# AtmoOrb.net
KiCad netlist of a schematic drawn in EAGLE
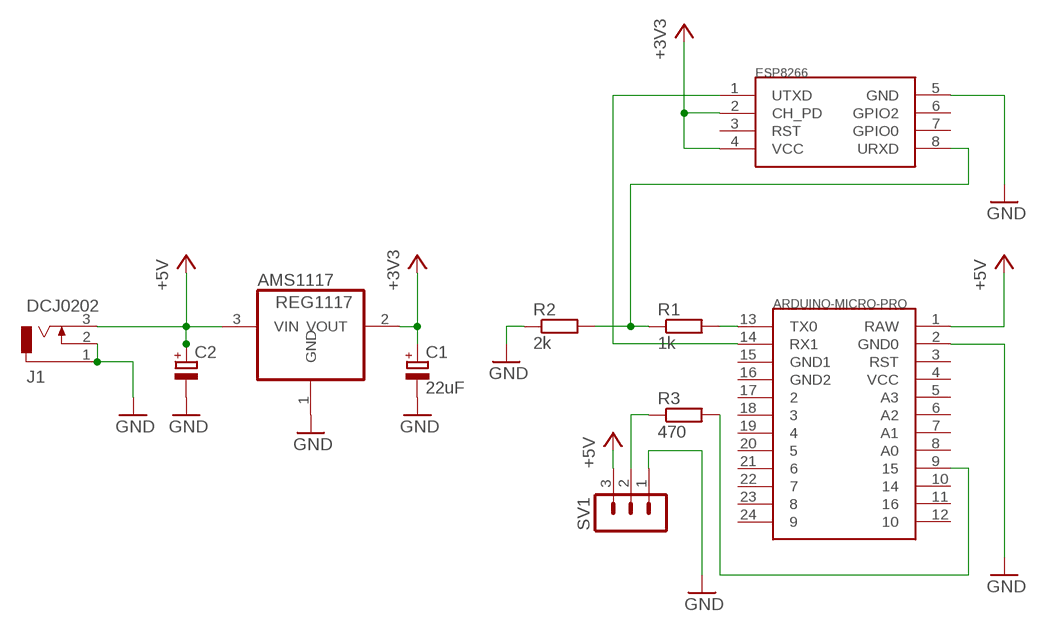
[diagram p0: schematic, sheet 1]

(export (version "E")
  (design (tool "Eeschema 10.0.6"))
  (components
    (comp (ref "AMS1117")
      (value "REG1117")
      (footprint "eagle-import:SOT223")
      (libsource (lib "eagle-import") (part "REG1117"))
    )
    (comp (ref "ARDUINO-MICRO-PRO")
      (value "ARDUINO_MICRO_PRO")
      (footprint "eagle-import:ARDUINO_MICRO_PRO")
      (libsource (lib "eagle-import") (part "ARDUINO_MICRO_PRO"))
    )
    (comp (ref "C1")
      (value "22uF")
      (footprint "eagle-import:TAP5-60")
      (libsource (lib "eagle-import") (part "CPOL-EUTAP5-60"))
    )
    (comp (ref "C2")
      (value "CPOL-EUTAP5-60")
      (footprint "eagle-import:TAP5-60")
      (libsource (lib "eagle-import") (part "CPOL-EUTAP5-60"))
    )
    (comp (ref "ESP8266")
      (value "ESP8266")
      (footprint "eagle-import:ESP8266")
      (libsource (lib "eagle-import") (part "ESP8266"))
    )
    (comp (ref "J1")
      (value "DCJ0202")
      (footprint "eagle-import:DCJ0202")
      (libsource (lib "eagle-import") (part "DCJ0202"))
    )
    (comp (ref "R1")
      (value "1k")
      (footprint "eagle-import:0207_10")
      (libsource (lib "eagle-import") (part "R-EU_0207/10"))
    )
    (comp (ref "R2")
      (value "2k")
      (footprint "eagle-import:0207_10")
      (libsource (lib "eagle-import") (part "R-EU_0207/10"))
    )
    (comp (ref "R3")
      (value "470")
      (footprint "eagle-import:0207_10")
      (libsource (lib "eagle-import") (part "R-EU_0207/10"))
    )
    (comp (ref "SV1")
      (value "MA03-1")
      (footprint "eagle-import:MA03-1")
      (libsource (lib "eagle-import") (part "MA03-1"))
    )
  )
  (nets
    (net (code "1") (name "+3V3") (class "Default")
      (node (ref "AMS1117") (pin "2") (pinfunction "VOUT_2") (pintype "output"))
      (node (ref "C1") (pin "+") (pinfunction "+_+") (pintype "passive"))
      (node (ref "ESP8266") (pin "2") (pinfunction "CH_PD_2") (pintype "bidirectional"))
      (node (ref "ESP8266") (pin "4") (pinfunction "VCC_4") (pintype "bidirectional"))
    )
    (net (code "2") (name "+5V") (class "Default")
      (node (ref "AMS1117") (pin "3") (pinfunction "VIN_3") (pintype "input"))
      (node (ref "ARDUINO-MICRO-PRO") (pin "1") (pinfunction "RAW_1") (pintype "bidirectional"))
      (node (ref "C2") (pin "+") (pinfunction "+_+") (pintype "passive"))
      (node (ref "J1") (pin "3") (pinfunction "3_3") (pintype "passive"))
      (node (ref "SV1") (pin "3") (pinfunction "3_3") (pintype "passive"))
    )
    (net (code "3") (name "GND") (class "Default")
      (node (ref "AMS1117") (pin "1") (pinfunction "GND_1") (pintype "power_in"))
      (node (ref "ARDUINO-MICRO-PRO") (pin "2") (pinfunction "GND0_2") (pintype "bidirectional"))
      (node (ref "C1") (pin "-") (pinfunction "-_-") (pintype "passive"))
      (node (ref "C2") (pin "-") (pinfunction "-_-") (pintype "passive"))
      (node (ref "ESP8266") (pin "5") (pinfunction "GND_5") (pintype "bidirectional"))
      (node (ref "J1") (pin "1") (pinfunction "1_1") (pintype "passive"))
      (node (ref "J1") (pin "2") (pinfunction "2_2") (pintype "passive"))
      (node (ref "R2") (pin "1") (pinfunction "1_1") (pintype "passive"))
      (node (ref "SV1") (pin "1") (pinfunction "1_1") (pintype "passive"))
    )
    (net (code "4") (name "Net-(ARDUINO-MICRO-PRO-15)") (class "Default")
      (node (ref "ARDUINO-MICRO-PRO") (pin "9") (pinfunction "15_9") (pintype "bidirectional"))
      (node (ref "R3") (pin "2") (pinfunction "2_2") (pintype "passive"))
    )
    (net (code "5") (name "Net-(ARDUINO-MICRO-PRO-RX1)") (class "Default")
      (node (ref "ARDUINO-MICRO-PRO") (pin "14") (pinfunction "RX1_14") (pintype "bidirectional"))
      (node (ref "ESP8266") (pin "1") (pinfunction "UTXD_1") (pintype "bidirectional"))
    )
    (net (code "6") (name "Net-(ARDUINO-MICRO-PRO-TX0)") (class "Default")
      (node (ref "ARDUINO-MICRO-PRO") (pin "13") (pinfunction "TX0_13") (pintype "bidirectional"))
      (node (ref "R1") (pin "2") (pinfunction "2_2") (pintype "passive"))
    )
    (net (code "7") (name "Net-(ESP8266-URXD)") (class "Default")
      (node (ref "ESP8266") (pin "8") (pinfunction "URXD_8") (pintype "bidirectional"))
      (node (ref "R1") (pin "1") (pinfunction "1_1") (pintype "passive"))
      (node (ref "R2") (pin "2") (pinfunction "2_2") (pintype "passive"))
    )
    (net (code "8") (name "Net-(R3-Pad1)") (class "Default")
      (node (ref "R3") (pin "1") (pinfunction "1_1") (pintype "passive"))
      (node (ref "SV1") (pin "2") (pinfunction "2_2") (pintype "passive"))
    )
    (net (code "9") (name "unconnected-(ARDUINO-MICRO-PRO-2-Pad17)") (class "Default")
      (node (ref "ARDUINO-MICRO-PRO") (pin "17") (pinfunction "2_17") (pintype "bidirectional"))
    )
    (net (code "10") (name "unconnected-(ARDUINO-MICRO-PRO-3-Pad18)") (class "Default")
      (node (ref "ARDUINO-MICRO-PRO") (pin "18") (pinfunction "3_18") (pintype "bidirectional"))
    )
    (net (code "11") (name "unconnected-(ARDUINO-MICRO-PRO-4-Pad19)") (class "Default")
      (node (ref "ARDUINO-MICRO-PRO") (pin "19") (pinfunction "4_19") (pintype "bidirectional"))
    )
    (net (code "12") (name "unconnected-(ARDUINO-MICRO-PRO-5-Pad20)") (class "Default")
      (node (ref "ARDUINO-MICRO-PRO") (pin "20") (pinfunction "5_20") (pintype "bidirectional"))
    )
    (net (code "13") (name "unconnected-(ARDUINO-MICRO-PRO-6-Pad21)") (class "Default")
      (node (ref "ARDUINO-MICRO-PRO") (pin "21") (pinfunction "6_21") (pintype "bidirectional"))
    )
    (net (code "14") (name "unconnected-(ARDUINO-MICRO-PRO-7-Pad22)") (class "Default")
      (node (ref "ARDUINO-MICRO-PRO") (pin "22") (pinfunction "7_22") (pintype "bidirectional"))
    )
    (net (code "15") (name "unconnected-(ARDUINO-MICRO-PRO-8-Pad23)") (class "Default")
      (node (ref "ARDUINO-MICRO-PRO") (pin "23") (pinfunction "8_23") (pintype "bidirectional"))
    )
    (net (code "16") (name "unconnected-(ARDUINO-MICRO-PRO-9-Pad24)") (class "Default")
      (node (ref "ARDUINO-MICRO-PRO") (pin "24") (pinfunction "9_24") (pintype "bidirectional"))
    )
    (net (code "17") (name "unconnected-(ARDUINO-MICRO-PRO-10-Pad12)") (class "Default")
      (node (ref "ARDUINO-MICRO-PRO") (pin "12") (pinfunction "10_12") (pintype "bidirectional"))
    )
    (net (code "18") (name "unconnected-(ARDUINO-MICRO-PRO-14-Pad10)") (class "Default")
      (node (ref "ARDUINO-MICRO-PRO") (pin "10") (pinfunction "14_10") (pintype "bidirectional"))
    )
    (net (code "19") (name "unconnected-(ARDUINO-MICRO-PRO-16-Pad11)") (class "Default")
      (node (ref "ARDUINO-MICRO-PRO") (pin "11") (pinfunction "16_11") (pintype "bidirectional"))
    )
    (net (code "20") (name "unconnected-(ARDUINO-MICRO-PRO-A0-Pad8)") (class "Default")
      (node (ref "ARDUINO-MICRO-PRO") (pin "8") (pinfunction "A0_8") (pintype "bidirectional"))
    )
    (net (code "21") (name "unconnected-(ARDUINO-MICRO-PRO-A1-Pad7)") (class "Default")
      (node (ref "ARDUINO-MICRO-PRO") (pin "7") (pinfunction "A1_7") (pintype "bidirectional"))
    )
    (net (code "22") (name "unconnected-(ARDUINO-MICRO-PRO-A2-Pad6)") (class "Default")
      (node (ref "ARDUINO-MICRO-PRO") (pin "6") (pinfunction "A2_6") (pintype "bidirectional"))
    )
    (net (code "23") (name "unconnected-(ARDUINO-MICRO-PRO-A3-Pad5)") (class "Default")
      (node (ref "ARDUINO-MICRO-PRO") (pin "5") (pinfunction "A3_5") (pintype "bidirectional"))
    )
    (net (code "24") (name "unconnected-(ARDUINO-MICRO-PRO-GND1-Pad15)") (class "Default")
      (node (ref "ARDUINO-MICRO-PRO") (pin "15") (pinfunction "GND1_15") (pintype "bidirectional"))
    )
    (net (code "25") (name "unconnected-(ARDUINO-MICRO-PRO-GND2-Pad16)") (class "Default")
      (node (ref "ARDUINO-MICRO-PRO") (pin "16") (pinfunction "GND2_16") (pintype "bidirectional"))
    )
    (net (code "26") (name "unconnected-(ARDUINO-MICRO-PRO-RST-Pad3)") (class "Default")
      (node (ref "ARDUINO-MICRO-PRO") (pin "3") (pinfunction "RST_3") (pintype "bidirectional"))
    )
    (net (code "27") (name "unconnected-(ARDUINO-MICRO-PRO-VCC-Pad4)") (class "Default")
      (node (ref "ARDUINO-MICRO-PRO") (pin "4") (pinfunction "VCC_4") (pintype "bidirectional"))
    )
    (net (code "28") (name "unconnected-(ESP8266-GPIO0-Pad7)") (class "Default")
      (node (ref "ESP8266") (pin "7") (pinfunction "GPIO0_7") (pintype "bidirectional"))
    )
    (net (code "29") (name "unconnected-(ESP8266-GPIO2-Pad6)") (class "Default")
      (node (ref "ESP8266") (pin "6") (pinfunction "GPIO2_6") (pintype "bidirectional"))
    )
    (net (code "30") (name "unconnected-(ESP8266-RST-Pad3)") (class "Default")
      (node (ref "ESP8266") (pin "3") (pinfunction "RST_3") (pintype "bidirectional"))
    )
  )
)
